# throughhole.net
KiCad netlist of a schematic drawn in EAGLE
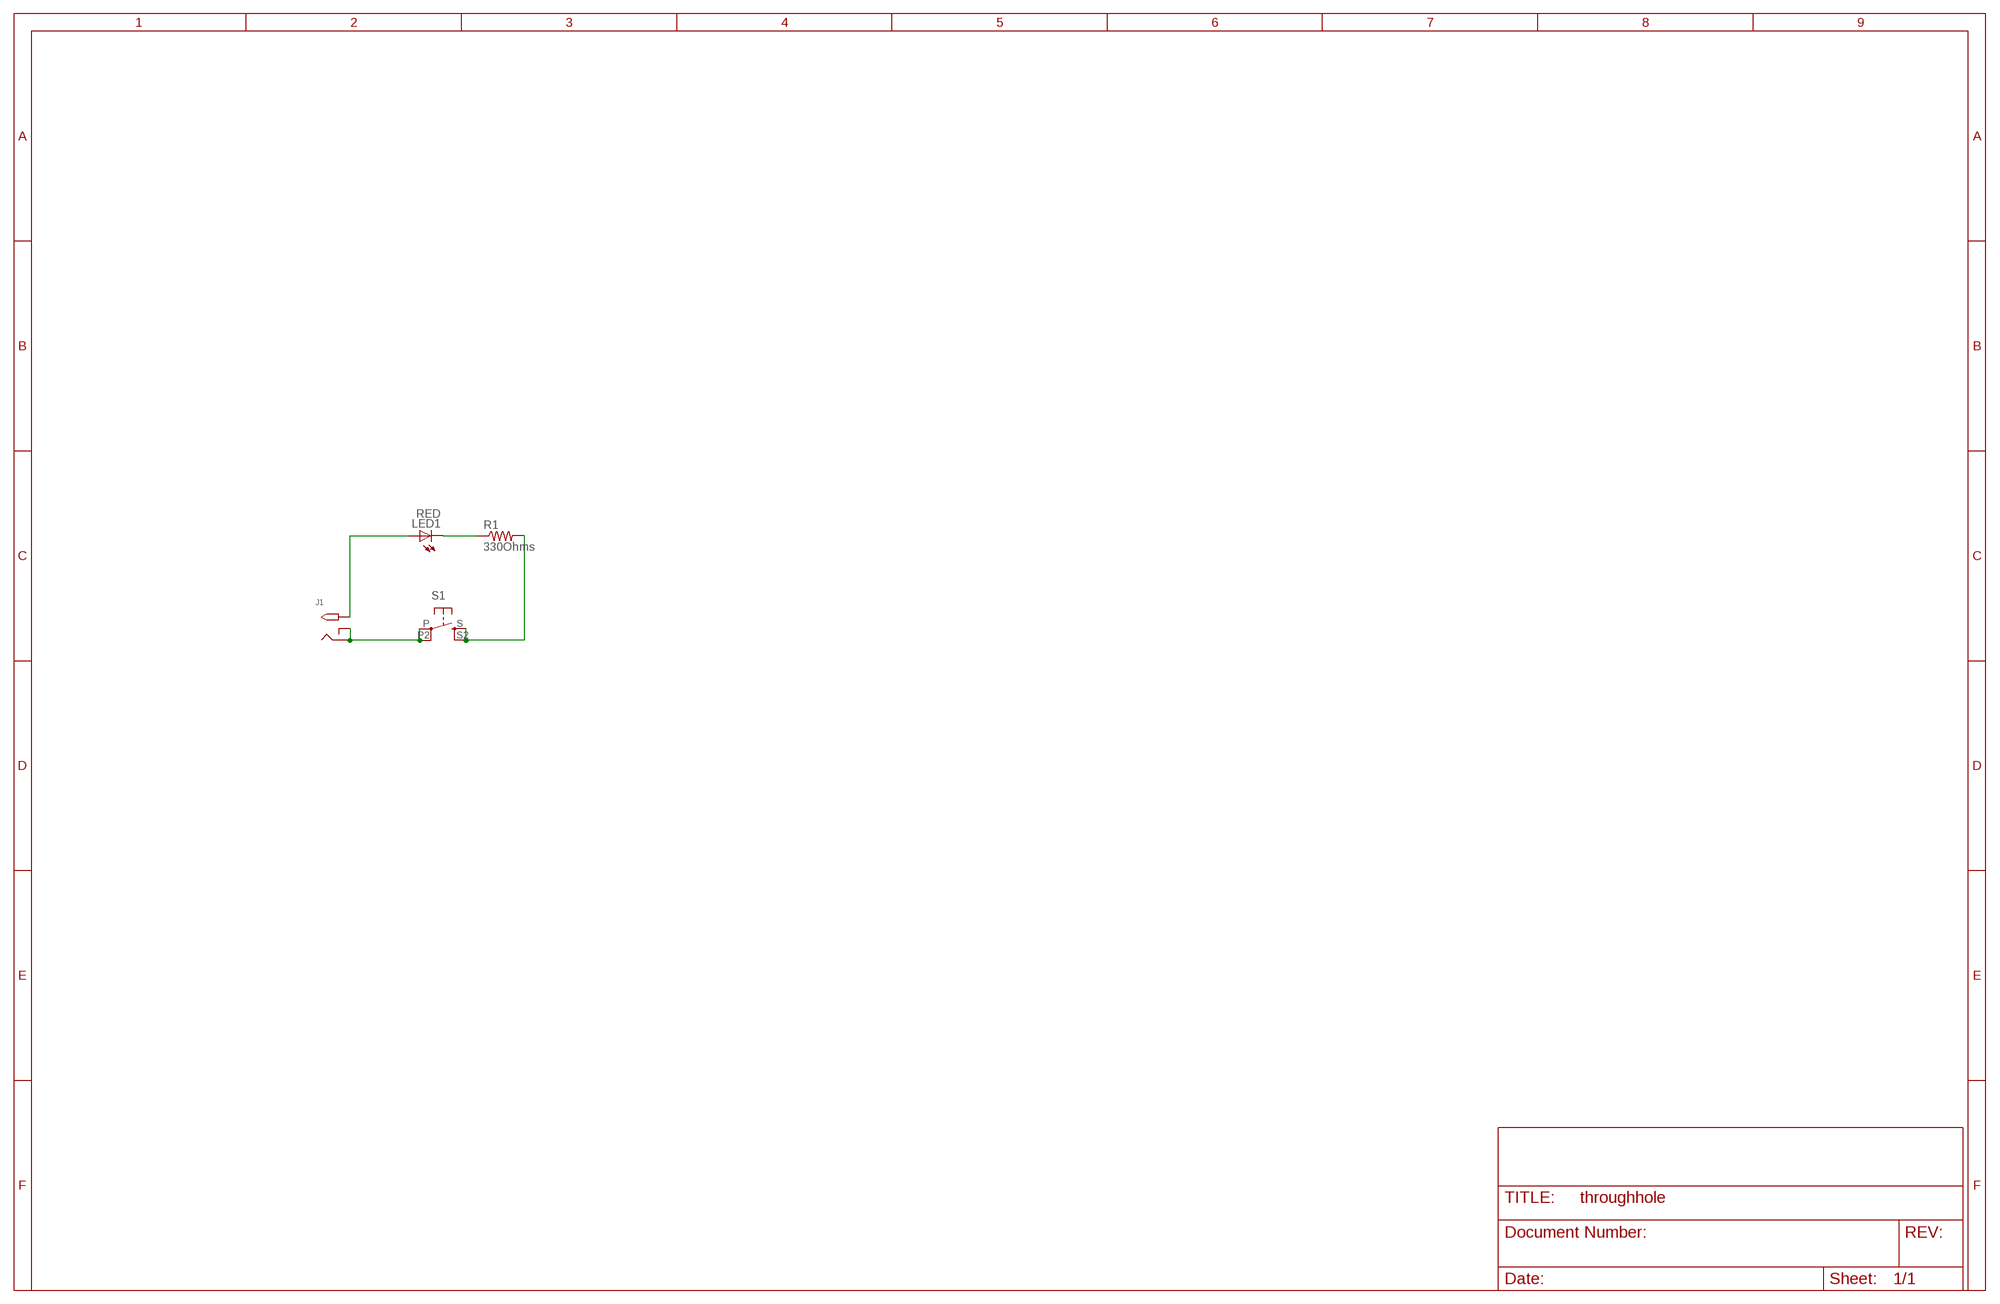
[diagram p0: schematic, sheet 1]

(export (version "E")
  (design (tool "Eeschema 10.0.6"))
  (components
    (comp (ref "J1")
      (value "2.1MMJACKTHM")
      (footprint "eagle-import:PJ-102A")
      (fields (field (name "CREATOR") "Swanson") (field (name "REVIEWER") "Swanson"))
      (libsource (lib "eagle-import") (part "2.1MMJACKTHM"))
    )
    (comp (ref "LED1")
      (value "RED")
      (footprint "eagle-import:LED5MM")
      (fields (field (name "CREATOR") "Swanson") (field (name "REVIEWER") "Swanson"))
      (libsource (lib "eagle-import") (part "LED5MM"))
    )
    (comp (ref "R1")
      (value "330Ohms")
      (footprint "eagle-import:RESAD1160W55L680D260_HS")
      (fields (field (name "CREATOR") "Swanson") (field (name "REVIEWER") "Swanson"))
      (libsource (lib "eagle-import") (part "RESISTORTH-1/4W-CARBON"))
    )
    (comp (ref "S1")
      (value "BUTTON-TACTILE-SQUARE")
      (footprint "eagle-import:BUTTON-TACTILE-SQUARE-ADAFRUIT1010")
      (fields (field (name "CREATOR") "Swanson") (field (name "REVIEWER") "Swanson"))
      (libsource (lib "eagle-import") (part "BUTTON-TACTILE-SQUARE"))
    )
  )
  (nets
    (net (code "1") (name "Net-(J1-PadTIP)") (class "Default")
      (node (ref "J1") (pin "TIP") (pinfunction "TIP_TIP") (pintype "bidirectional"))
      (node (ref "LED1") (pin "A") (pinfunction "A_A") (pintype "passive"))
    )
    (net (code "2") (name "Net-(LED1-C)") (class "Default")
      (node (ref "LED1") (pin "K") (pinfunction "C_K") (pintype "passive"))
      (node (ref "R1") (pin "1") (pinfunction "1_1") (pintype "passive"))
    )
    (net (code "3") (name "Net-(S1-P1)") (class "Default")
      (node (ref "J1") (pin "RING") (pinfunction "RING_RING") (pintype "bidirectional"))
      (node (ref "J1") (pin "RING_SW") (pinfunction "RING_SW_RING_SW") (pintype "bidirectional"))
      (node (ref "S1") (pin "P") (pinfunction "P_P") (pintype "passive"))
      (node (ref "S1") (pin "P2") (pinfunction "P1_P2") (pintype "passive"))
    )
    (net (code "4") (name "Net-(S1-S1)") (class "Default")
      (node (ref "R1") (pin "2") (pinfunction "2_2") (pintype "passive"))
      (node (ref "S1") (pin "S") (pinfunction "S_S") (pintype "passive"))
      (node (ref "S1") (pin "S2") (pinfunction "S1_S2") (pintype "passive"))
    )
  )
)
